# CC-S12-V00-PowerSwitch.net
KiCad netlist of a schematic drawn in Altium Designer
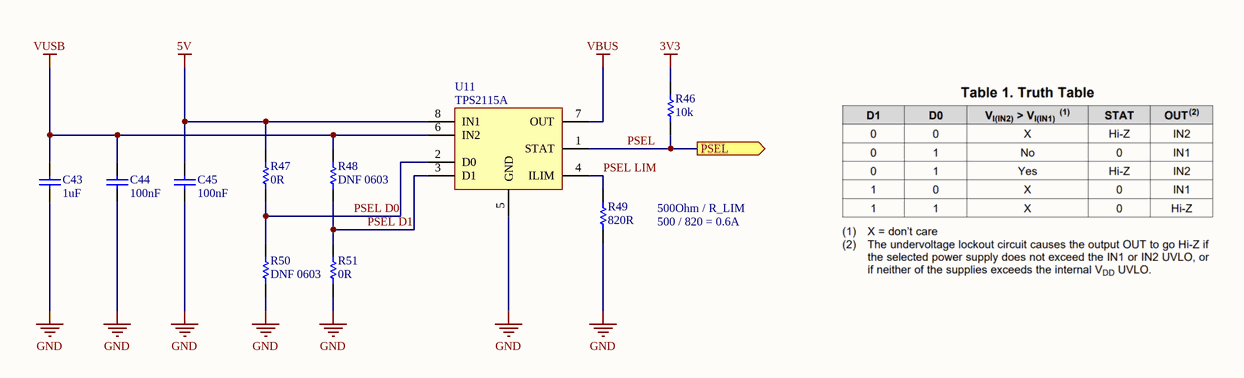
[diagram p0: CC-S12-V00-PowerSwitch.SchDoc]

(export (version "E")
  (design (tool "Eeschema 10.0.6"))
  (components
    (comp (ref "C43")
      (value "1uF")
      (footprint "Cap_Ceramic_0603")
      (description "Capacitor, Ceramic, SMD, 1uF, 25V, 5%, X7R, 0603")
      (libsource (lib "StandardCapacitors") (part "1uF 25V 5% X7R 0603"))
    )
    (comp (ref "C44")
      (value "100nF")
      (footprint "Cap_Ceramic_0603")
      (description "Capacitor, Ceramic, SMD, 100nF, 50V, 5%, X7R, 0603")
      (libsource (lib "StandardCapacitors") (part "100nF 50V 5% X7R 0603"))
    )
    (comp (ref "C45")
      (value "100nF")
      (footprint "Cap_Ceramic_0603")
      (description "Capacitor, Ceramic, SMD, 100nF, 50V, 5%, X7R, 0603")
      (libsource (lib "StandardCapacitors") (part "100nF 50V 5% X7R 0603"))
    )
    (comp (ref "R46")
      (value "10k")
      (footprint "Res_ThinFilm_0603")
      (description "Resistor, SMD, 10k, 0.1W, 5%, 0603")
      (libsource (lib "StandardResistors") (part "10k 5% 0603"))
    )
    (comp (ref "R47")
      (value "0R")
      (footprint "Res_ThinFilm_0603")
      (description "Resistor, SMD, 0R, 0.1W, 5%, 0603")
      (libsource (lib "StandardResistors") (part "0R 5% 0603"))
    )
    (comp (ref "R48")
      (value "DNF 0603")
      (footprint "Res_ThinFilm_0603")
      (description "Resistor, SMD, DNF, 0.1W, 0603")
      (libsource (lib "StandardResistors") (part "DNF 0603"))
    )
    (comp (ref "R49")
      (value "820R")
      (footprint "Res_ThinFilm_0603")
      (description "Resistor, SMD, 820R, 0.1W, 5%, 0603")
      (libsource (lib "StandardResistors") (part "820R 5% 0603"))
    )
    (comp (ref "R50")
      (value "DNF 0603")
      (footprint "Res_ThinFilm_0603")
      (description "Resistor, SMD, DNF, 0.1W, 0603")
      (libsource (lib "StandardResistors") (part "DNF 0603"))
    )
    (comp (ref "R51")
      (value "0R")
      (footprint "Res_ThinFilm_0603")
      (description "Resistor, SMD, 0R, 0.1W, 5%, 0603")
      (libsource (lib "StandardResistors") (part "0R 5% 0603"))
    )
    (comp (ref "U11")
      (value "TPS2115A")
      (footprint "TPS2115A")
      (description "OR Controller Source Selector Switch N-Channel 2:1 8-TSSOP")
      (libsource (lib "QUTMS_PowerSupplyLibrary") (part "TPS2115A"))
    )
  )
  (nets
    (net (code "1") (name "/PSEL") (class "Default")
      (node (ref "R46") (pin "1") (pinfunction "1_1") (pintype "passive"))
      (node (ref "U11") (pin "1") (pinfunction "STAT_1") (pintype "passive"))
    )
    (net (code "2") (name "/PSEL D0") (class "Default")
      (node (ref "R47") (pin "1") (pinfunction "1_1") (pintype "passive"))
      (node (ref "R50") (pin "2") (pinfunction "2_2") (pintype "passive"))
      (node (ref "U11") (pin "2") (pinfunction "D0_2") (pintype "passive"))
    )
    (net (code "3") (name "/PSEL D1") (class "Default")
      (node (ref "R48") (pin "1") (pinfunction "1_1") (pintype "passive"))
      (node (ref "R51") (pin "2") (pinfunction "2_2") (pintype "passive"))
      (node (ref "U11") (pin "3") (pinfunction "D1_3") (pintype "passive"))
    )
    (net (code "4") (name "/PSEL LIM") (class "Default")
      (node (ref "R49") (pin "2") (pinfunction "2_2") (pintype "passive"))
      (node (ref "U11") (pin "4") (pinfunction "ILIM_4") (pintype "passive"))
    )
    (net (code "5") (name "3V3") (class "Default")
      (node (ref "R46") (pin "2") (pinfunction "2_2") (pintype "passive"))
    )
    (net (code "6") (name "5V") (class "Default")
      (node (ref "C45") (pin "2") (pinfunction "2_2") (pintype "passive"))
      (node (ref "R47") (pin "2") (pinfunction "2_2") (pintype "passive"))
      (node (ref "U11") (pin "8") (pinfunction "IN1_8") (pintype "passive"))
    )
    (net (code "7") (name "GND") (class "Default")
      (node (ref "C43") (pin "1") (pinfunction "1_1") (pintype "passive"))
      (node (ref "C44") (pin "1") (pinfunction "1_1") (pintype "passive"))
      (node (ref "C45") (pin "1") (pinfunction "1_1") (pintype "passive"))
      (node (ref "R49") (pin "1") (pinfunction "1_1") (pintype "passive"))
      (node (ref "R50") (pin "1") (pinfunction "1_1") (pintype "passive"))
      (node (ref "R51") (pin "1") (pinfunction "1_1") (pintype "passive"))
      (node (ref "U11") (pin "5") (pinfunction "GND_5") (pintype "passive"))
    )
    (net (code "8") (name "VBUS") (class "Default")
      (node (ref "U11") (pin "7") (pinfunction "OUT_7") (pintype "passive"))
    )
    (net (code "9") (name "VUSB") (class "Default")
      (node (ref "C43") (pin "2") (pinfunction "2_2") (pintype "passive"))
      (node (ref "C44") (pin "2") (pinfunction "2_2") (pintype "passive"))
      (node (ref "R48") (pin "2") (pinfunction "2_2") (pintype "passive"))
      (node (ref "U11") (pin "6") (pinfunction "IN2_6") (pintype "passive"))
    )
  )
)
